# LEDS_PCB.net
KiCad netlist of a schematic drawn in EAGLE
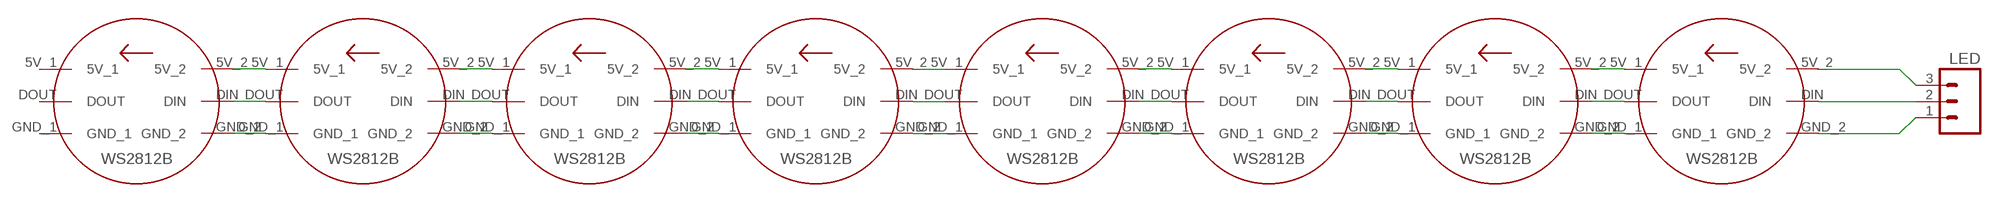
[diagram p0: schematic, sheet 1]

(export (version "E")
  (design (tool "Eeschema 10.0.6"))
  (components
    (comp (ref "LED")
      (value "M03PTH")
      (footprint "eagle-import:1X03")
      (libsource (lib "eagle-import") (part "M03PTH"))
    )
    (comp (ref "U$1")
      (value "WS2812B_LED")
      (footprint "eagle-import:CIRCLE_PCB")
      (libsource (lib "eagle-import") (part "WS2812B_LED"))
    )
    (comp (ref "U$2")
      (value "WS2812B_LED")
      (footprint "eagle-import:CIRCLE_PCB")
      (libsource (lib "eagle-import") (part "WS2812B_LED"))
    )
    (comp (ref "U$3")
      (value "WS2812B_LED")
      (footprint "eagle-import:CIRCLE_PCB")
      (libsource (lib "eagle-import") (part "WS2812B_LED"))
    )
    (comp (ref "U$4")
      (value "WS2812B_LED")
      (footprint "eagle-import:CIRCLE_PCB")
      (libsource (lib "eagle-import") (part "WS2812B_LED"))
    )
    (comp (ref "U$5")
      (value "WS2812B_LED")
      (footprint "eagle-import:CIRCLE_PCB")
      (libsource (lib "eagle-import") (part "WS2812B_LED"))
    )
    (comp (ref "U$6")
      (value "WS2812B_LED")
      (footprint "eagle-import:CIRCLE_PCB")
      (libsource (lib "eagle-import") (part "WS2812B_LED"))
    )
    (comp (ref "U$7")
      (value "WS2812B_LED")
      (footprint "eagle-import:CIRCLE_PCB")
      (libsource (lib "eagle-import") (part "WS2812B_LED"))
    )
    (comp (ref "U$8")
      (value "WS2812B_LED")
      (footprint "eagle-import:CIRCLE_PCB")
      (libsource (lib "eagle-import") (part "WS2812B_LED"))
    )
  )
  (nets
    (net (code "1") (name "Net-(LED-Pad1)") (class "Default")
      (node (ref "LED") (pin "1") (pinfunction "1_1") (pintype "passive"))
      (node (ref "U$1") (pin "GND_2") (pinfunction "GND_2_GND_2") (pintype "bidirectional"))
    )
    (net (code "2") (name "Net-(LED-Pad2)") (class "Default")
      (node (ref "LED") (pin "2") (pinfunction "2_2") (pintype "passive"))
      (node (ref "U$1") (pin "DIN") (pinfunction "DIN_DIN") (pintype "bidirectional"))
    )
    (net (code "3") (name "Net-(LED-Pad3)") (class "Default")
      (node (ref "LED") (pin "3") (pinfunction "3_3") (pintype "passive"))
      (node (ref "U$1") (pin "5V_2") (pinfunction "5V_2_5V_2") (pintype "bidirectional"))
    )
    (net (code "4") (name "Net-(U$1-Pad5V_1)") (class "Default")
      (node (ref "U$1") (pin "5V_1") (pinfunction "5V_1_5V_1") (pintype "bidirectional"))
      (node (ref "U$2") (pin "5V_2") (pinfunction "5V_2_5V_2") (pintype "bidirectional"))
    )
    (net (code "5") (name "Net-(U$1-PadDOUT)") (class "Default")
      (node (ref "U$1") (pin "DOUT") (pinfunction "DOUT_DOUT") (pintype "bidirectional"))
      (node (ref "U$2") (pin "DIN") (pinfunction "DIN_DIN") (pintype "bidirectional"))
    )
    (net (code "6") (name "Net-(U$1-PadGND_1)") (class "Default")
      (node (ref "U$1") (pin "GND_1") (pinfunction "GND_1_GND_1") (pintype "bidirectional"))
      (node (ref "U$2") (pin "GND_2") (pinfunction "GND_2_GND_2") (pintype "bidirectional"))
    )
    (net (code "7") (name "Net-(U$2-Pad5V_1)") (class "Default")
      (node (ref "U$2") (pin "5V_1") (pinfunction "5V_1_5V_1") (pintype "bidirectional"))
      (node (ref "U$3") (pin "5V_2") (pinfunction "5V_2_5V_2") (pintype "bidirectional"))
    )
    (net (code "8") (name "Net-(U$2-PadDOUT)") (class "Default")
      (node (ref "U$2") (pin "DOUT") (pinfunction "DOUT_DOUT") (pintype "bidirectional"))
      (node (ref "U$3") (pin "DIN") (pinfunction "DIN_DIN") (pintype "bidirectional"))
    )
    (net (code "9") (name "Net-(U$2-PadGND_1)") (class "Default")
      (node (ref "U$2") (pin "GND_1") (pinfunction "GND_1_GND_1") (pintype "bidirectional"))
      (node (ref "U$3") (pin "GND_2") (pinfunction "GND_2_GND_2") (pintype "bidirectional"))
    )
    (net (code "10") (name "Net-(U$3-Pad5V_1)") (class "Default")
      (node (ref "U$3") (pin "5V_1") (pinfunction "5V_1_5V_1") (pintype "bidirectional"))
      (node (ref "U$4") (pin "5V_2") (pinfunction "5V_2_5V_2") (pintype "bidirectional"))
    )
    (net (code "11") (name "Net-(U$3-PadDOUT)") (class "Default")
      (node (ref "U$3") (pin "DOUT") (pinfunction "DOUT_DOUT") (pintype "bidirectional"))
      (node (ref "U$4") (pin "DIN") (pinfunction "DIN_DIN") (pintype "bidirectional"))
    )
    (net (code "12") (name "Net-(U$3-PadGND_1)") (class "Default")
      (node (ref "U$3") (pin "GND_1") (pinfunction "GND_1_GND_1") (pintype "bidirectional"))
      (node (ref "U$4") (pin "GND_2") (pinfunction "GND_2_GND_2") (pintype "bidirectional"))
    )
    (net (code "13") (name "Net-(U$4-Pad5V_1)") (class "Default")
      (node (ref "U$4") (pin "5V_1") (pinfunction "5V_1_5V_1") (pintype "bidirectional"))
      (node (ref "U$5") (pin "5V_2") (pinfunction "5V_2_5V_2") (pintype "bidirectional"))
    )
    (net (code "14") (name "Net-(U$4-PadDOUT)") (class "Default")
      (node (ref "U$4") (pin "DOUT") (pinfunction "DOUT_DOUT") (pintype "bidirectional"))
      (node (ref "U$5") (pin "DIN") (pinfunction "DIN_DIN") (pintype "bidirectional"))
    )
    (net (code "15") (name "Net-(U$4-PadGND_1)") (class "Default")
      (node (ref "U$4") (pin "GND_1") (pinfunction "GND_1_GND_1") (pintype "bidirectional"))
      (node (ref "U$5") (pin "GND_2") (pinfunction "GND_2_GND_2") (pintype "bidirectional"))
    )
    (net (code "16") (name "Net-(U$5-Pad5V_1)") (class "Default")
      (node (ref "U$5") (pin "5V_1") (pinfunction "5V_1_5V_1") (pintype "bidirectional"))
      (node (ref "U$6") (pin "5V_2") (pinfunction "5V_2_5V_2") (pintype "bidirectional"))
    )
    (net (code "17") (name "Net-(U$5-PadDOUT)") (class "Default")
      (node (ref "U$5") (pin "DOUT") (pinfunction "DOUT_DOUT") (pintype "bidirectional"))
      (node (ref "U$6") (pin "DIN") (pinfunction "DIN_DIN") (pintype "bidirectional"))
    )
    (net (code "18") (name "Net-(U$5-PadGND_1)") (class "Default")
      (node (ref "U$5") (pin "GND_1") (pinfunction "GND_1_GND_1") (pintype "bidirectional"))
      (node (ref "U$6") (pin "GND_2") (pinfunction "GND_2_GND_2") (pintype "bidirectional"))
    )
    (net (code "19") (name "Net-(U$6-Pad5V_1)") (class "Default")
      (node (ref "U$6") (pin "5V_1") (pinfunction "5V_1_5V_1") (pintype "bidirectional"))
      (node (ref "U$7") (pin "5V_2") (pinfunction "5V_2_5V_2") (pintype "bidirectional"))
    )
    (net (code "20") (name "Net-(U$6-PadDOUT)") (class "Default")
      (node (ref "U$6") (pin "DOUT") (pinfunction "DOUT_DOUT") (pintype "bidirectional"))
      (node (ref "U$7") (pin "DIN") (pinfunction "DIN_DIN") (pintype "bidirectional"))
    )
    (net (code "21") (name "Net-(U$6-PadGND_1)") (class "Default")
      (node (ref "U$6") (pin "GND_1") (pinfunction "GND_1_GND_1") (pintype "bidirectional"))
      (node (ref "U$7") (pin "GND_2") (pinfunction "GND_2_GND_2") (pintype "bidirectional"))
    )
    (net (code "22") (name "Net-(U$7-Pad5V_1)") (class "Default")
      (node (ref "U$7") (pin "5V_1") (pinfunction "5V_1_5V_1") (pintype "bidirectional"))
      (node (ref "U$8") (pin "5V_2") (pinfunction "5V_2_5V_2") (pintype "bidirectional"))
    )
    (net (code "23") (name "Net-(U$7-PadDOUT)") (class "Default")
      (node (ref "U$7") (pin "DOUT") (pinfunction "DOUT_DOUT") (pintype "bidirectional"))
      (node (ref "U$8") (pin "DIN") (pinfunction "DIN_DIN") (pintype "bidirectional"))
    )
    (net (code "24") (name "Net-(U$7-PadGND_1)") (class "Default")
      (node (ref "U$7") (pin "GND_1") (pinfunction "GND_1_GND_1") (pintype "bidirectional"))
      (node (ref "U$8") (pin "GND_2") (pinfunction "GND_2_GND_2") (pintype "bidirectional"))
    )
    (net (code "25") (name "unconnected-(U$8-Pad5V_1)") (class "Default")
      (node (ref "U$8") (pin "5V_1") (pinfunction "5V_1_5V_1") (pintype "bidirectional"))
    )
    (net (code "26") (name "unconnected-(U$8-PadDOUT)") (class "Default")
      (node (ref "U$8") (pin "DOUT") (pinfunction "DOUT_DOUT") (pintype "bidirectional"))
    )
    (net (code "27") (name "unconnected-(U$8-PadGND_1)") (class "Default")
      (node (ref "U$8") (pin "GND_1") (pinfunction "GND_1_GND_1") (pintype "bidirectional"))
    )
  )
)
